# POWER.net
KiCad netlist of a schematic drawn in Altium Designer
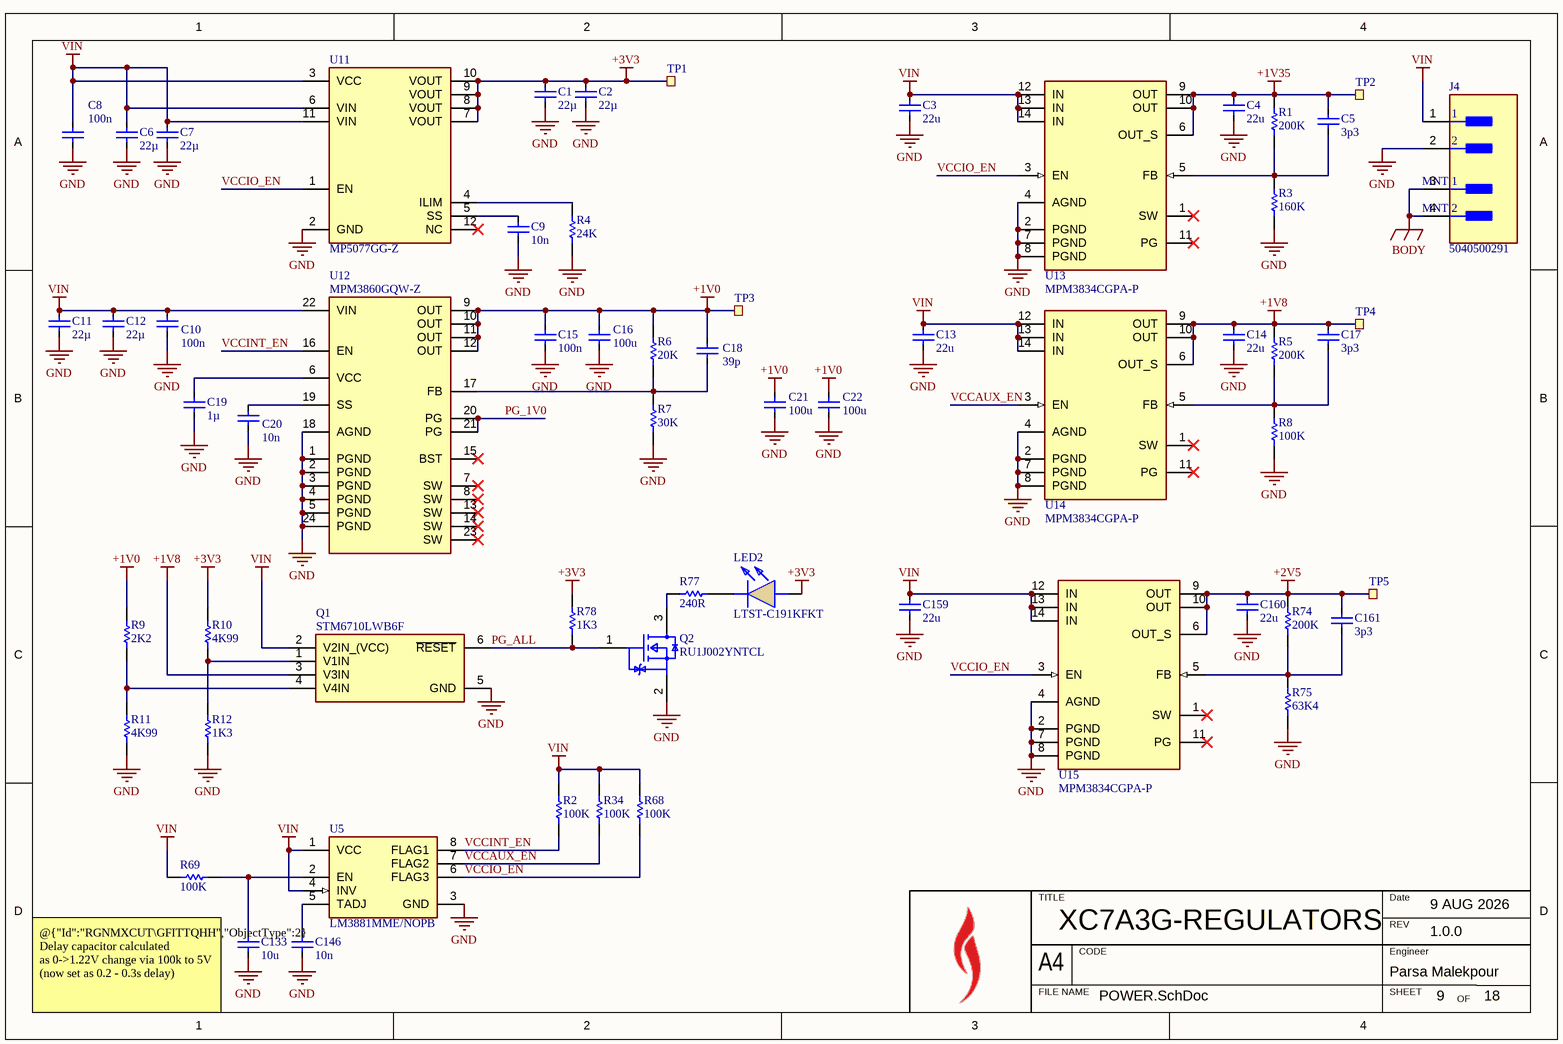
[diagram p0: POWER.SchDoc]

(export (version "E")
  (design (tool "Eeschema 10.0.6"))
  (components
    (comp (ref "C1")
      (value "22µ")
      (footprint "CAPC1608X100X20LL10")
      (description "MLCC 22 uF, ±20%, 6.3 V, -55 to 85 degC, 1608 (0603 Metric), RoHS, Tape and Reel")
      (fields
        (field (name "TOLERANCE") "±20%")
        (field (name "PCN PART NUMBER") "MLCCPartNumberChange30/Nov/2012")
      )
      (libsource (lib "Schlib1") (part "C1608X5R0J226M080AC"))
    )
    (comp (ref "C2")
      (value "22µ")
      (footprint "CAPC1608X100X20LL10")
      (description "MLCC 22 uF, ±20%, 6.3 V, -55 to 85 degC, 1608 (0603 Metric), RoHS, Tape and Reel")
      (fields
        (field (name "TOLERANCE") "±20%")
        (field (name "PCN PART NUMBER") "MLCCPartNumberChange30/Nov/2012")
      )
      (libsource (lib "Schlib1") (part "C1608X5R0J226M080AC"))
    )
    (comp (ref "C3")
      (value "22u")
      (footprint "CAPC1608X100X20LL10")
      (description "MLCC 22 uF, ±20%, 6.3 V, -55 to 85 degC, 1608 (0603 Metric), RoHS, Tape and Reel")
      (fields
        (field (name "TOLERANCE") "±20%")
        (field (name "PCN PART NUMBER") "MLCCPartNumberChange30/Nov/2012")
      )
      (libsource (lib "Schlib1") (part "C1608X5R0J226M080AC"))
    )
    (comp (ref "C4")
      (value "22u")
      (footprint "CAPC1608X100X20LL10")
      (description "MLCC 22 uF, ±20%, 6.3 V, -55 to 85 degC, 1608 (0603 Metric), RoHS, Tape and Reel")
      (fields
        (field (name "TOLERANCE") "±20%")
        (field (name "PCN PART NUMBER") "MLCCPartNumberChange30/Nov/2012")
      )
      (libsource (lib "Schlib1") (part "C1608X5R0J226M080AC"))
    )
    (comp (ref "C5")
      (value "3p3")
      (footprint "PCBLIB1:CAPC1005X55N")
      (description "Capacitor")
      (fields (field (name "PART NUMBER") "CGA2B2C0G1H3R3C050BA"))
      (libsource (lib "Schlib1") (part "CGA2B2C0G1H3R3C050BA"))
    )
    (comp (ref "C6")
      (value "22µ")
      (footprint "CAPC1608X100X20LL10")
      (description "MLCC 22 uF, ±20%, 6.3 V, -55 to 85 degC, 1608 (0603 Metric), RoHS, Tape and Reel")
      (fields
        (field (name "TOLERANCE") "±20%")
        (field (name "PCN PART NUMBER") "MLCCPartNumberChange30/Nov/2012")
      )
      (libsource (lib "Schlib1") (part "C1608X5R0J226M080AC"))
    )
    (comp (ref "C7")
      (value "22µ")
      (footprint "CAPC1608X100X20LL10")
      (description "MLCC 22 uF, ±20%, 6.3 V, -55 to 85 degC, 1608 (0603 Metric), RoHS, Tape and Reel")
      (fields
        (field (name "TOLERANCE") "±20%")
        (field (name "PCN PART NUMBER") "MLCCPartNumberChange30/Nov/2012")
      )
      (libsource (lib "Schlib1") (part "C1608X5R0J226M080AC"))
    )
    (comp (ref "C8")
      (value "100n")
      (footprint "FP-C1005-050-0_05-IPC_C")
      (description "MLCC 100nF ±10% 50V X7R SMD 0402")
      (fields (field (name "VOLTAGE") "50V") (field (name "TOLERANCE") "10%"))
      (libsource (lib "Schlib1") (part "C1005X7R1H104K050BB"))
    )
    (comp (ref "C9")
      (value "10n")
      (footprint "FP-C1005-050-0_05-IPC_C")
      (description "MLCC 10nF ±10% 100V X7S SMD 0402")
      (fields (field (name "TOLERANCE") "10%") (field (name "VOLTAGE") "100V"))
      (libsource (lib "Schlib1") (part "C1005X7S2A103K050BB"))
    )
    (comp (ref "C10")
      (value "100n")
      (footprint "FP-C1005-050-0_05-IPC_C")
      (description "MLCC 100nF ±10% 50V X7R SMD 0402")
      (fields (field (name "VOLTAGE") "50V") (field (name "TOLERANCE") "10%"))
      (libsource (lib "Schlib1") (part "C1005X7R1H104K050BB"))
    )
    (comp (ref "C11")
      (value "22µ")
      (footprint "CAPC1608X100X20LL10")
      (description "MLCC 22 uF, ±20%, 6.3 V, -55 to 85 degC, 1608 (0603 Metric), RoHS, Tape and Reel")
      (fields
        (field (name "TOLERANCE") "±20%")
        (field (name "PCN PART NUMBER") "MLCCPartNumberChange30/Nov/2012")
      )
      (libsource (lib "Schlib1") (part "C1608X5R0J226M080AC"))
    )
    (comp (ref "C12")
      (value "22µ")
      (footprint "CAPC1608X100X20LL10")
      (description "MLCC 22 uF, ±20%, 6.3 V, -55 to 85 degC, 1608 (0603 Metric), RoHS, Tape and Reel")
      (fields
        (field (name "TOLERANCE") "±20%")
        (field (name "PCN PART NUMBER") "MLCCPartNumberChange30/Nov/2012")
      )
      (libsource (lib "Schlib1") (part "C1608X5R0J226M080AC"))
    )
    (comp (ref "C13")
      (value "22u")
      (footprint "CAPC1608X100X20LL10")
      (description "MLCC 22 uF, ±20%, 6.3 V, -55 to 85 degC, 1608 (0603 Metric), RoHS, Tape and Reel")
      (fields
        (field (name "TOLERANCE") "±20%")
        (field (name "PCN PART NUMBER") "MLCCPartNumberChange30/Nov/2012")
      )
      (libsource (lib "Schlib1") (part "C1608X5R0J226M080AC"))
    )
    (comp (ref "C14")
      (value "22u")
      (footprint "CAPC1608X100X20LL10")
      (description "MLCC 22 uF, ±20%, 6.3 V, -55 to 85 degC, 1608 (0603 Metric), RoHS, Tape and Reel")
      (fields
        (field (name "TOLERANCE") "±20%")
        (field (name "PCN PART NUMBER") "MLCCPartNumberChange30/Nov/2012")
      )
      (libsource (lib "Schlib1") (part "C1608X5R0J226M080AC"))
    )
    (comp (ref "C15")
      (value "100n")
      (footprint "FP-C1005-050-0_05-IPC_C")
      (description "MLCC 100nF ±10% 50V X7R SMD 0402")
      (fields (field (name "VOLTAGE") "50V") (field (name "TOLERANCE") "10%"))
      (libsource (lib "Schlib1") (part "C1005X7R1H104K050BB"))
    )
    (comp (ref "C16")
      (value "100u")
      (footprint "FP-C3216-160-0_3-IPC_B")
      (description "MLCC 100uF ±20% 4V X5R SMD 1206")
      (fields (field (name "TOLERANCE") "20%") (field (name "PART NUMBER") "C3216X5R0G107M160AB"))
      (libsource (lib "Schlib1") (part "C3216X5R0G107M160AB"))
    )
    (comp (ref "C17")
      (value "3p3")
      (footprint "PCBLIB1:CAPC1005X55N")
      (description "Capacitor")
      (fields (field (name "PART NUMBER") "CGA2B2C0G1H3R3C050BA"))
      (libsource (lib "Schlib1") (part "CGA2B2C0G1H3R3C050BA"))
    )
    (comp (ref "C18")
      (value "39p")
      (footprint "FP-C1005-050-0_05-IPC_C")
      (description "MLCC 39pF ±5% 50V C0G SMD 0402")
      (fields (field (name "TOLERANCE") "5%") (field (name "PART NUMBER") "C1005C0G1H390J050BA"))
      (libsource (lib "Schlib1") (part "C1005C0G1H390J050BA"))
    )
    (comp (ref "C19")
      (value "1µ")
      (footprint "pcblib1:CAPC1005X55X10NL05")
      (description "MLCC 1 uF, +/- 10%, 10 V, -55 to 85 degC, 0402 (1005 Metric), RoHS, Tape and Reel")
      (fields (field (name "MANUFACTURER") "TDK") (field (name "TOLERANCE") "±10%"))
      (libsource (lib "Schlib1") (part "C1005X5R1A105K050BB"))
    )
    (comp (ref "C20")
      (value "10n")
      (footprint "FP-C1005-050-0_05-IPC_C")
      (description "MLCC 10nF ±10% 100V X7S SMD 0402")
      (fields (field (name "TOLERANCE") "10%") (field (name "VOLTAGE") "100V"))
      (libsource (lib "Schlib1") (part "C1005X7S2A103K050BB"))
    )
    (comp (ref "C21")
      (value "100u")
      (footprint "FP-C3216-160-0_3-IPC_B")
      (description "MLCC 100uF ±20% 4V X5R SMD 1206")
      (fields (field (name "TOLERANCE") "20%") (field (name "PART NUMBER") "C3216X5R0G107M160AB"))
      (libsource (lib "Schlib1") (part "C3216X5R0G107M160AB"))
    )
    (comp (ref "C22")
      (value "100u")
      (footprint "FP-C3216-160-0_3-IPC_B")
      (description "MLCC 100uF ±20% 4V X5R SMD 1206")
      (fields (field (name "TOLERANCE") "20%") (field (name "PART NUMBER") "C3216X5R0G107M160AB"))
      (libsource (lib "Schlib1") (part "C3216X5R0G107M160AB"))
    )
    (comp (ref "C133")
      (value "10u")
      (footprint "FP-C1608-080-0_1-IPC_C")
      (description "MLCC 10μF ±10% 6.3V JB SMD 0603")
      (fields (field (name "TOLERANCE") "10%") (field (name "Comment") "C1608JB0J106K080AB"))
      (libsource (lib "Schlib1") (part "C1608JB0J106K080AB"))
    )
    (comp (ref "C146")
      (value "10n")
      (footprint "FP-C1005-050-0_05-IPC_C")
      (description "MLCC 10nF ±10% 100V X7S SMD 0402")
      (fields (field (name "TOLERANCE") "10%") (field (name "VOLTAGE") "100V"))
      (libsource (lib "Schlib1") (part "C1005X7S2A103K050BB"))
    )
    (comp (ref "C159")
      (value "22u")
      (footprint "CAPC1608X100X20NL10")
      (description "MLCC 22 uF, ±20%, 6.3 V, -55 to 85 degC, 1608 (0603 Metric), RoHS, Tape and Reel")
      (fields
        (field (name "TOLERANCE") "±20%")
        (field (name "PCN PART NUMBER") "MLCCPartNumberChange30/Nov/2012")
      )
      (libsource (lib "Schlib1") (part "C1608X5R0J226M080AC"))
    )
    (comp (ref "C160")
      (value "22u")
      (footprint "CAPC1608X100X20LL10")
      (description "MLCC 22 uF, ±20%, 6.3 V, -55 to 85 degC, 1608 (0603 Metric), RoHS, Tape and Reel")
      (fields
        (field (name "TOLERANCE") "±20%")
        (field (name "PCN PART NUMBER") "MLCCPartNumberChange30/Nov/2012")
      )
      (libsource (lib "Schlib1") (part "C1608X5R0J226M080AC"))
    )
    (comp (ref "C161")
      (value "3p3")
      (footprint "PCBLIB1:CAPC1005X55N")
      (description "Capacitor")
      (fields (field (name "PART NUMBER") "CGA2B2C0G1H3R3C050BA"))
      (libsource (lib "Schlib1") (part "CGA2B2C0G1H3R3C050BA"))
    )
    (comp (ref "J4")
      (value "5040500291")
      (footprint "FP-5040500291-MFG")
      (description "CONN HEADER SMD R/A 2POS 1.5MM")
      (fields
        (field (name "OCTOPART") "https://octopart.com/504050-0291-molex-99548498")
        (field (name "MANUFACTURER") "Molex")
      )
      (libsource (lib "Schlib1") (part "5040500291"))
    )
    (comp (ref "LED2")
      (value "LTST-C191KFKT")
      (footprint "LEDC1608X55N")
      (description "LED")
      (fields (field (name "MOUSER PART NUMBER") "859-LTST-C191KFKT") (field (name "MANUFACTURER") "Lite-On"))
      (libsource (lib "Schlib1") (part "LTST-C191KFKT"))
    )
    (comp (ref "Q1")
      (value "STM6710LWB6F")
      (footprint "SOT95P280X145-6N")
      (description "Transistor")
      (fields (field (name "MOUSER PART NUMBER") "511-STM6710LWB6F"))
      (libsource (lib "Schlib1") (part "STM6710LWB6F"))
    )
    (comp (ref "Q2")
      (value "RU1J002YNTCL")
      (footprint "FP-UMT3F-MFG")
      (description "MOSFET N-CH 50V 0.2A UMT3F")
      (fields
        (field (name "MANUFACTURER") "Rohm")
        (field (name "OCTOPART") "https://octopart.com/ru1j002yntcl-rohm-47197697")
      )
      (libsource (lib "Schlib1") (part "RU1J002YNTCL"))
    )
    (comp (ref "R1")
      (value "200K")
      (footprint "RESC1005X40X25NL05T10")
      (fields (field (name "PART NUMBER") "RC0402FR-07200KL") (field (name "MANUFACTURER") "Yageo / Phycomp"))
      (libsource (lib "Schlib1") (part "RC0402FR-07200KL"))
    )
    (comp (ref "R2")
      (value "100K")
      (footprint "RESC1005X40X25LL05T10")
      (fields (field (name "PART NUMBER") "RC0402FR-07100KL") (field (name "MANUFACTURER") "Yageo / Phycomp"))
      (libsource (lib "Schlib1") (part "RC0402FR-07100KL"))
    )
    (comp (ref "R3")
      (value "160K")
      (footprint "RESC1005X40X25NL05T10")
      (fields (field (name "PART NUMBER") "RC0402FR-07160KL") (field (name "MANUFACTURER") "Yageo / Phycomp"))
      (libsource (lib "Schlib1") (part "RC0402FR-07160KL"))
    )
    (comp (ref "R4")
      (value "24K")
      (footprint "RESC1005X40X25LL05T10")
      (fields (field (name "MANUFACTURER") "Yageo / Phycomp") (field (name "PART NUMBER") "RC0402FR-0724KL"))
      (libsource (lib "Schlib1") (part "RC0402FR-0724KL"))
    )
    (comp (ref "R5")
      (value "200K")
      (footprint "RESC1005X40X25LL05T10")
      (fields (field (name "PART NUMBER") "RC0402FR-07200KL") (field (name "MANUFACTURER") "Yageo / Phycomp"))
      (libsource (lib "Schlib1") (part "RC0402FR-07200KL"))
    )
    (comp (ref "R6")
      (value "20K")
      (footprint "RESC1005X40X25LL05T10")
      (fields (field (name "MANUFACTURER") "Yageo / Phycomp") (field (name "PART NUMBER") "RC0402FR-0720KL"))
      (libsource (lib "Schlib1") (part "RC0402FR-0720KL"))
    )
    (comp (ref "R7")
      (value "30K")
      (footprint "RESC1005X40X25LL05T10")
      (fields (field (name "MANUFACTURER") "Yageo / Phycomp") (field (name "PART NUMBER") "RC0402FR-0730KL"))
      (libsource (lib "Schlib1") (part "RC0402FR-0730KL"))
    )
    (comp (ref "R8")
      (value "100K")
      (footprint "RESC1005X40X25LL05T10")
      (fields (field (name "PART NUMBER") "RC0402FR-07100KL") (field (name "MANUFACTURER") "Yageo / Phycomp"))
      (libsource (lib "Schlib1") (part "RC0402FR-07100KL"))
    )
    (comp (ref "R9")
      (value "2K2")
      (footprint "RESC1005X40X25LL05T10")
      (fields (field (name "MANUFACTURER") "Yageo / Phycomp") (field (name "PART NUMBER") "RC0402FR-072K2L"))
      (libsource (lib "Schlib1") (part "RC0402FR-072K2L"))
    )
    (comp (ref "R10")
      (value "4K99")
      (footprint "RESC1005X40X25LL05T10")
      (fields (field (name "MANUFACTURER") "Yageo / Phycomp") (field (name "PART NUMBER") "RC0402FR-074K99L"))
      (libsource (lib "Schlib1") (part "RC0402FR-074K99L"))
    )
    (comp (ref "R11")
      (value "4K99")
      (footprint "PCBLIB1:RESC1005X40X25LL05T10")
      (fields (field (name "MANUFACTURER") "Yageo / Phycomp") (field (name "PART NUMBER") "RC0402FR-074K99L"))
      (libsource (lib "Schlib1") (part "RC0402FR-074K99L"))
    )
    (comp (ref "R12")
      (value "1K3")
      (footprint "RESC1005X40X25LL05T10")
      (fields (field (name "MANUFACTURER") "Yageo / Phycomp") (field (name "PART NUMBER") "RC0402FR-071K3L"))
      (libsource (lib "Schlib1") (part "RC0402FR-071K3L"))
    )
    (comp (ref "R34")
      (value "100K")
      (footprint "RESC1005X40X25LL05T10")
      (fields (field (name "PART NUMBER") "RC0402FR-07100KL") (field (name "MANUFACTURER") "Yageo / Phycomp"))
      (libsource (lib "Schlib1") (part "RC0402FR-07100KL"))
    )
    (comp (ref "R68")
      (value "100K")
      (footprint "RESC1005X40X25LL05T10")
      (fields (field (name "PART NUMBER") "RC0402FR-07100KL") (field (name "MANUFACTURER") "Yageo / Phycomp"))
      (libsource (lib "Schlib1") (part "RC0402FR-07100KL"))
    )
    (comp (ref "R69")
      (value "100K")
      (footprint "RESC1005X40X25NL05T10")
      (fields (field (name "PART NUMBER") "RC0402FR-07100KL") (field (name "MANUFACTURER") "Yageo / Phycomp"))
      (libsource (lib "Schlib1") (part "RC0402FR-07100KL"))
    )
    (comp (ref "R74")
      (value "200K")
      (footprint "RESC1005X40X25NL05T10")
      (fields (field (name "PART NUMBER") "RC0402FR-07200KL") (field (name "MANUFACTURER") "Yageo / Phycomp"))
      (libsource (lib "Schlib1") (part "RC0402FR-07200KL"))
    )
    (comp (ref "R75")
      (value "63K4")
      (footprint "RESC1005X40X25ML05T10")
      (fields (field (name "MANUFACTURER") "Yageo / Phycomp") (field (name "PART NUMBER") "RC0402FR-0763K4L"))
      (libsource (lib "Schlib1") (part "RC0402FR-0763K4L"))
    )
    (comp (ref "R77")
      (value "240R")
      (footprint "pcblib1:RESC1005X40X25LL05T10")
      (description "240R 0.063W 1% 0402 (1005 Metric)  SMD")
      (fields (field (name "POWER") "0.063 W") (field (name "TOLERANCE") "1 %"))
      (libsource (lib "Schlib1") (part "RC0402FR-07240RL"))
    )
    (comp (ref "R78")
      (value "1K3")
      (footprint "RESC1005X40X25LL05T10")
      (fields (field (name "MANUFACTURER") "Yageo / Phycomp") (field (name "PART NUMBER") "RC0402FR-071K3L"))
      (libsource (lib "Schlib1") (part "RC0402FR-071K3L"))
    )
    (comp (ref "TP1")
      (value "Ø1.0mm,SMD")
      (footprint "TP_SMD_Ø1.0mm")
      (description "1.0mm circular SMD testpad")
      (fields
        (field (name "PART NUMBER") "TP_SMD_Ø1.0MM")
        (field (name "MANUFACTURER") "Nordic Semiconductor")
      )
      (libsource (lib "ParsaLibrary") (part "TP_SMD_Ø1.0MM"))
    )
    (comp (ref "TP2")
      (value "Ø1.0mm,SMD")
      (footprint "TP_SMD_Ø1.0mm")
      (description "1.0mm circular SMD testpad")
      (fields
        (field (name "PART NUMBER") "TP_SMD_Ø1.0MM")
        (field (name "MANUFACTURER") "Nordic Semiconductor")
      )
      (libsource (lib "ParsaLibrary") (part "TP_SMD_Ø1.0MM"))
    )
    (comp (ref "TP3")
      (value "Ø1.0mm,SMD")
      (footprint "TP_SMD_Ø1.0mm")
      (description "1.0mm circular SMD testpad")
      (fields
        (field (name "PART NUMBER") "TP_SMD_Ø1.0MM")
        (field (name "MANUFACTURER") "Nordic Semiconductor")
      )
      (libsource (lib "ParsaLibrary") (part "TP_SMD_Ø1.0MM"))
    )
    (comp (ref "TP4")
      (value "Ø1.0mm,SMD")
      (footprint "TP_SMD_Ø1.0mm")
      (description "1.0mm circular SMD testpad")
      (fields
        (field (name "PART NUMBER") "TP_SMD_Ø1.0MM")
        (field (name "MANUFACTURER") "Nordic Semiconductor")
      )
      (libsource (lib "ParsaLibrary") (part "TP_SMD_Ø1.0MM"))
    )
    (comp (ref "TP5")
      (value "Ø1.0mm,SMD")
      (footprint "TP_SMD_Ø1.0mm")
      (description "1.0mm circular SMD testpad")
      (fields
        (field (name "PART NUMBER") "TP_SMD_Ø1.0MM")
        (field (name "MANUFACTURER") "Nordic Semiconductor")
      )
      (libsource (lib "ParsaLibrary") (part "TP_SMD_Ø1.0MM"))
    )
    (comp (ref "U5")
      (value "LM3881MME/NOPB")
      (footprint "FP-DGK0008A-MFG")
      (description "IC POWER SUPPLY SEQUENCER 8VSSOP")
      (fields
        (field (name "OCTOPART") "https://octopart.com/lm3881mme%2Fnopb-texas+instruments-24814197")
        (field (name "MANUFACTURER") "Texas Instruments")
      )
      (libsource (lib "Schlib1") (part "LM3881MME/NOPB"))
    )
    (comp (ref "U11")
      (value "MP5077GG-Z")
      (footprint "MP5077GGZ")
      (description "Integrated Circuit")
      (fields (field (name "MOUSER PART NUMBER") "946-MP5077GG-Z"))
      (libsource (lib "Schlib1") (part "MP5077GG-Z"))
    )
    (comp (ref "U12")
      (value "MPM3860GQW-Z")
      (footprint "MPM3650CGQWZ")
      (description "Integrated Circuit")
      (fields (field (name "MOUSER PART NUMBER") "946-MPM3860GQW-Z"))
      (libsource (lib "Schlib1") (part "MPM3860GQW-Z"))
    )
    (comp (ref "U13")
      (value "MPM3834CGPA-P")
      (footprint "MPM3834CGPAP")
      (description "Integrated Circuit")
      (fields (field (name "MOUSER PART NUMBER") "946-MPM3834CGPA-P"))
      (libsource (lib "Schlib1") (part "MPM3834CGPA-P"))
    )
    (comp (ref "U14")
      (value "MPM3834CGPA-P")
      (footprint "MPM3834CGPAP")
      (description "Integrated Circuit")
      (fields (field (name "MOUSER PART NUMBER") "946-MPM3834CGPA-P"))
      (libsource (lib "Schlib1") (part "MPM3834CGPA-P"))
    )
    (comp (ref "U15")
      (value "MPM3834CGPA-P")
      (footprint "MPM3834CGPAP")
      (description "Integrated Circuit")
      (fields (field (name "MOUSER PART NUMBER") "946-MPM3834CGPA-P"))
      (libsource (lib "Schlib1") (part "MPM3834CGPA-P"))
    )
  )
  (nets
    (net (code "1") (name "+1V0") (class "Default")
      (node (ref "C15") (pin "1") (pinfunction "1_1") (pintype "passive"))
      (node (ref "C16") (pin "2") (pinfunction "2_2") (pintype "passive"))
      (node (ref "C18") (pin "2") (pinfunction "2_2") (pintype "passive"))
      (node (ref "C21") (pin "2") (pinfunction "2_2") (pintype "passive"))
      (node (ref "C22") (pin "2") (pinfunction "2_2") (pintype "passive"))
      (node (ref "R6") (pin "1") (pinfunction "1_1") (pintype "passive"))
      (node (ref "R9") (pin "1") (pinfunction "1_1") (pintype "passive"))
      (node (ref "TP3") (pin "1") (pinfunction "1_1") (pintype "passive"))
      (node (ref "U12") (pin "10") (pinfunction "OUT_10") (pintype "passive"))
      (node (ref "U12") (pin "11") (pinfunction "OUT_11") (pintype "passive"))
      (node (ref "U12") (pin "12") (pinfunction "OUT_12") (pintype "passive"))
      (node (ref "U12") (pin "9") (pinfunction "OUT_9") (pintype "passive"))
    )
    (net (code "2") (name "+1V8") (class "Default")
      (node (ref "C14") (pin "1") (pinfunction "1_1") (pintype "passive"))
      (node (ref "C17") (pin "1") (pinfunction "1_1") (pintype "passive"))
      (node (ref "Q1") (pin "3") (pinfunction "V3IN_3") (pintype "passive"))
      (node (ref "R5") (pin "1") (pinfunction "1_1") (pintype "passive"))
      (node (ref "TP4") (pin "1") (pinfunction "1_1") (pintype "passive"))
      (node (ref "U14") (pin "10") (pinfunction "OUT_10") (pintype "power_in"))
      (node (ref "U14") (pin "6") (pinfunction "OUT_S_6") (pintype "passive"))
      (node (ref "U14") (pin "9") (pinfunction "OUT_9") (pintype "power_in"))
    )
    (net (code "3") (name "+1V35") (class "Default")
      (node (ref "C4") (pin "1") (pinfunction "1_1") (pintype "passive"))
      (node (ref "C5") (pin "1") (pinfunction "1_1") (pintype "passive"))
      (node (ref "R1") (pin "1") (pinfunction "1_1") (pintype "passive"))
      (node (ref "TP2") (pin "1") (pinfunction "1_1") (pintype "passive"))
      (node (ref "U13") (pin "10") (pinfunction "OUT_10") (pintype "power_in"))
      (node (ref "U13") (pin "6") (pinfunction "OUT_S_6") (pintype "passive"))
      (node (ref "U13") (pin "9") (pinfunction "OUT_9") (pintype "power_in"))
    )
    (net (code "4") (name "+2V5") (class "Default")
      (node (ref "C160") (pin "1") (pinfunction "1_1") (pintype "passive"))
      (node (ref "C161") (pin "1") (pinfunction "1_1") (pintype "passive"))
      (node (ref "R74") (pin "1") (pinfunction "1_1") (pintype "passive"))
      (node (ref "TP5") (pin "1") (pinfunction "1_1") (pintype "passive"))
      (node (ref "U15") (pin "10") (pinfunction "OUT_10") (pintype "power_in"))
      (node (ref "U15") (pin "6") (pinfunction "OUT_S_6") (pintype "passive"))
      (node (ref "U15") (pin "9") (pinfunction "OUT_9") (pintype "power_in"))
    )
    (net (code "5") (name "+3V3") (class "Default")
      (node (ref "C1") (pin "1") (pinfunction "1_1") (pintype "passive"))
      (node (ref "C2") (pin "1") (pinfunction "1_1") (pintype "passive"))
      (node (ref "LED2") (pin "2") (pinfunction "A_2") (pintype "passive"))
      (node (ref "R10") (pin "1") (pinfunction "1_1") (pintype "passive"))
      (node (ref "R78") (pin "1") (pinfunction "1_1") (pintype "passive"))
      (node (ref "TP1") (pin "1") (pinfunction "1_1") (pintype "passive"))
      (node (ref "U11") (pin "10") (pinfunction "VOUT_10") (pintype "passive"))
      (node (ref "U11") (pin "7") (pinfunction "VOUT_7") (pintype "passive"))
      (node (ref "U11") (pin "8") (pinfunction "VOUT_8") (pintype "passive"))
      (node (ref "U11") (pin "9") (pinfunction "VOUT_9") (pintype "passive"))
    )
    (net (code "6") (name "/PG_1V0") (class "Default")
      (node (ref "U12") (pin "20") (pinfunction "PG_20") (pintype "passive"))
      (node (ref "U12") (pin "21") (pinfunction "PG_21") (pintype "passive"))
    )
    (net (code "7") (name "/PG_ALL") (class "Default")
      (node (ref "Q1") (pin "6") (pinfunction "~{RESET}_6") (pintype "passive"))
      (node (ref "Q2") (pin "1") (pinfunction "G_1") (pintype "passive"))
      (node (ref "R78") (pin "2") (pinfunction "2_2") (pintype "passive"))
    )
    (net (code "8") (name "/VCCAUX_EN") (class "Default")
      (node (ref "R34") (pin "2") (pinfunction "2_2") (pintype "passive"))
      (node (ref "U14") (pin "3") (pinfunction "EN_3") (pintype "input"))
      (node (ref "U5") (pin "7") (pinfunction "FLAG2_7") (pintype "open_collector"))
    )
    (net (code "9") (name "/VCCINT_EN") (class "Default")
      (node (ref "R2") (pin "2") (pinfunction "2_2") (pintype "passive"))
      (node (ref "U12") (pin "16") (pinfunction "EN_16") (pintype "passive"))
      (node (ref "U5") (pin "8") (pinfunction "FLAG1_8") (pintype "open_collector"))
    )
    (net (code "10") (name "/VCCIO_EN") (class "Default")
      (node (ref "R68") (pin "2") (pinfunction "2_2") (pintype "passive"))
      (node (ref "U11") (pin "1") (pinfunction "EN_1") (pintype "passive"))
      (node (ref "U13") (pin "3") (pinfunction "EN_3") (pintype "input"))
      (node (ref "U15") (pin "3") (pinfunction "EN_3") (pintype "input"))
      (node (ref "U5") (pin "6") (pinfunction "FLAG3_6") (pintype "open_collector"))
    )
    (net (code "11") (name "BODY") (class "Default")
      (node (ref "J4") (pin "3") (pinfunction "MNT_1_3") (pintype "passive"))
      (node (ref "J4") (pin "4") (pinfunction "MNT_2_4") (pintype "passive"))
    )
    (net (code "12") (name "GND") (class "Default")
      (node (ref "C1") (pin "2") (pinfunction "2_2") (pintype "passive"))
      (node (ref "C10") (pin "1") (pinfunction "1_1") (pintype "passive"))
      (node (ref "C11") (pin "2") (pinfunction "2_2") (pintype "passive"))
      (node (ref "C12") (pin "2") (pinfunction "2_2") (pintype "passive"))
      (node (ref "C13") (pin "2") (pinfunction "2_2") (pintype "passive"))
      (node (ref "C133") (pin "2") (pinfunction "2_2") (pintype "passive"))
      (node (ref "C14") (pin "2") (pinfunction "2_2") (pintype "passive"))
      (node (ref "C146") (pin "2") (pinfunction "2_2") (pintype "passive"))
      (node (ref "C15") (pin "2") (pinfunction "2_2") (pintype "passive"))
      (node (ref "C159") (pin "2") (pinfunction "2_2") (pintype "passive"))
      (node (ref "C16") (pin "1") (pinfunction "1_1") (pintype "passive"))
      (node (ref "C160") (pin "2") (pinfunction "2_2") (pintype "passive"))
      (node (ref "C19") (pin "2") (pinfunction "2_2") (pintype "passive"))
      (node (ref "C2") (pin "2") (pinfunction "2_2") (pintype "passive"))
      (node (ref "C20") (pin "1") (pinfunction "1_1") (pintype "passive"))
      (node (ref "C21") (pin "1") (pinfunction "1_1") (pintype "passive"))
      (node (ref "C22") (pin "1") (pinfunction "1_1") (pintype "passive"))
      (node (ref "C3") (pin "2") (pinfunction "2_2") (pintype "passive"))
      (node (ref "C4") (pin "2") (pinfunction "2_2") (pintype "passive"))
      (node (ref "C6") (pin "2") (pinfunction "2_2") (pintype "passive"))
      (node (ref "C7") (pin "2") (pinfunction "2_2") (pintype "passive"))
      (node (ref "C8") (pin "1") (pinfunction "1_1") (pintype "passive"))
      (node (ref "C9") (pin "2") (pinfunction "2_2") (pintype "passive"))
      (node (ref "J4") (pin "2") (pinfunction "2_2") (pintype "passive"))
      (node (ref "Q1") (pin "5") (pinfunction "GND_5") (pintype "passive"))
      (node (ref "Q2") (pin "2") (pinfunction "S_2") (pintype "passive"))
      (node (ref "R11") (pin "2") (pinfunction "2_2") (pintype "passive"))
      (node (ref "R12") (pin "1") (pinfunction "1_1") (pintype "passive"))
      (node (ref "R3") (pin "2") (pinfunction "2_2") (pintype "passive"))
      (node (ref "R4") (pin "2") (pinfunction "2_2") (pintype "passive"))
      (node (ref "R7") (pin "2") (pinfunction "2_2") (pintype "passive"))
      (node (ref "R75") (pin "2") (pinfunction "2_2") (pintype "passive"))
      (node (ref "R8") (pin "2") (pinfunction "2_2") (pintype "passive"))
      (node (ref "U11") (pin "2") (pinfunction "GND_2") (pintype "passive"))
      (node (ref "U12") (pin "1") (pinfunction "PGND_1") (pintype "passive"))
      (node (ref "U12") (pin "18") (pinfunction "AGND_18") (pintype "passive"))
      (node (ref "U12") (pin "2") (pinfunction "PGND_2") (pintype "passive"))
      (node (ref "U12") (pin "24") (pinfunction "PGND_24") (pintype "passive"))
      (node (ref "U12") (pin "3") (pinfunction "PGND_3") (pintype "passive"))
      (node (ref "U12") (pin "4") (pinfunction "PGND_4") (pintype "passive"))
      (node (ref "U12") (pin "5") (pinfunction "PGND_5") (pintype "passive"))
      (node (ref "U13") (pin "2") (pinfunction "PGND_2") (pintype "power_in"))
      (node (ref "U13") (pin "4") (pinfunction "AGND_4") (pintype "passive"))
      (node (ref "U13") (pin "7") (pinfunction "PGND_7") (pintype "power_in"))
      (node (ref "U13") (pin "8") (pinfunction "PGND_8") (pintype "power_in"))
      (node (ref "U14") (pin "2") (pinfunction "PGND_2") (pintype "power_in"))
      (node (ref "U14") (pin "4") (pinfunction "AGND_4") (pintype "passive"))
      (node (ref "U14") (pin "7") (pinfunction "PGND_7") (pintype "power_in"))
      (node (ref "U14") (pin "8") (pinfunction "PGND_8") (pintype "power_in"))
      (node (ref "U15") (pin "2") (pinfunction "PGND_2") (pintype "power_in"))
      (node (ref "U15") (pin "4") (pinfunction "AGND_4") (pintype "passive"))
      (node (ref "U15") (pin "7") (pinfunction "PGND_7") (pintype "power_in"))
      (node (ref "U15") (pin "8") (pinfunction "PGND_8") (pintype "power_in"))
      (node (ref "U5") (pin "3") (pinfunction "GND_3") (pintype "power_in"))
    )
    (net (code "13") (name "Net-(LED2-K)") (class "Default")
      (node (ref "LED2") (pin "1") (pinfunction "K_1") (pintype "passive"))
      (node (ref "R77") (pin "1") (pinfunction "1_1") (pintype "passive"))
    )
    (net (code "14") (name "Net-(Q1-V1IN)") (class "Default")
      (node (ref "Q1") (pin "1") (pinfunction "V1IN_1") (pintype "passive"))
      (node (ref "R10") (pin "2") (pinfunction "2_2") (pintype "passive"))
      (node (ref "R12") (pin "2") (pinfunction "2_2") (pintype "passive"))
    )
    (net (code "15") (name "Net-(Q1-V4IN)") (class "Default")
      (node (ref "Q1") (pin "4") (pinfunction "V4IN_4") (pintype "passive"))
      (node (ref "R11") (pin "1") (pinfunction "1_1") (pintype "passive"))
      (node (ref "R9") (pin "2") (pinfunction "2_2") (pintype "passive"))
    )
    (net (code "16") (name "Net-(Q2-D)") (class "Default")
      (node (ref "Q2") (pin "3") (pinfunction "D_3") (pintype "passive"))
      (node (ref "R77") (pin "2") (pinfunction "2_2") (pintype "passive"))
    )
    (net (code "17") (name "Net-(U5-EN)") (class "Default")
      (node (ref "C133") (pin "1") (pinfunction "1_1") (pintype "passive"))
      (node (ref "R69") (pin "2") (pinfunction "2_2") (pintype "passive"))
      (node (ref "U5") (pin "2") (pinfunction "EN_2") (pintype "passive"))
    )
    (net (code "18") (name "Net-(U5-TADJ)") (class "Default")
      (node (ref "C146") (pin "1") (pinfunction "1_1") (pintype "passive"))
      (node (ref "U5") (pin "5") (pinfunction "TADJ_5") (pintype "passive"))
    )
    (net (code "19") (name "Net-(U11-ILIM)") (class "Default")
      (node (ref "R4") (pin "1") (pinfunction "1_1") (pintype "passive"))
      (node (ref "U11") (pin "4") (pinfunction "ILIM_4") (pintype "passive"))
    )
    (net (code "20") (name "Net-(U11-SS)") (class "Default")
      (node (ref "C9") (pin "1") (pinfunction "1_1") (pintype "passive"))
      (node (ref "U11") (pin "5") (pinfunction "SS_5") (pintype "passive"))
    )
    (net (code "21") (name "Net-(U12-FB)") (class "Default")
      (node (ref "C18") (pin "1") (pinfunction "1_1") (pintype "passive"))
      (node (ref "R6") (pin "2") (pinfunction "2_2") (pintype "passive"))
      (node (ref "R7") (pin "1") (pinfunction "1_1") (pintype "passive"))
      (node (ref "U12") (pin "17") (pinfunction "FB_17") (pintype "passive"))
    )
    (net (code "22") (name "Net-(U12-SS)") (class "Default")
      (node (ref "C20") (pin "2") (pinfunction "2_2") (pintype "passive"))
      (node (ref "U12") (pin "19") (pinfunction "SS_19") (pintype "passive"))
    )
    (net (code "23") (name "Net-(U12-VCC)") (class "Default")
      (node (ref "C19") (pin "1") (pinfunction "1_1") (pintype "passive"))
      (node (ref "U12") (pin "6") (pinfunction "VCC_6") (pintype "passive"))
    )
    (net (code "24") (name "Net-(U13-FB)") (class "Default")
      (node (ref "C5") (pin "2") (pinfunction "2_2") (pintype "passive"))
      (node (ref "R1") (pin "2") (pinfunction "2_2") (pintype "passive"))
      (node (ref "R3") (pin "1") (pinfunction "1_1") (pintype "passive"))
      (node (ref "U13") (pin "5") (pinfunction "FB_5") (pintype "input"))
    )
    (net (code "25") (name "Net-(U14-FB)") (class "Default")
      (node (ref "C17") (pin "2") (pinfunction "2_2") (pintype "passive"))
      (node (ref "R5") (pin "2") (pinfunction "2_2") (pintype "passive"))
      (node (ref "R8") (pin "1") (pinfunction "1_1") (pintype "passive"))
      (node (ref "U14") (pin "5") (pinfunction "FB_5") (pintype "input"))
    )
    (net (code "26") (name "Net-(U15-FB)") (class "Default")
      (node (ref "C161") (pin "2") (pinfunction "2_2") (pintype "passive"))
      (node (ref "R74") (pin "2") (pinfunction "2_2") (pintype "passive"))
      (node (ref "R75") (pin "1") (pinfunction "1_1") (pintype "passive"))
      (node (ref "U15") (pin "5") (pinfunction "FB_5") (pintype "input"))
    )
    (net (code "27") (name "VIN") (class "Default")
      (node (ref "C10") (pin "2") (pinfunction "2_2") (pintype "passive"))
      (node (ref "C11") (pin "1") (pinfunction "1_1") (pintype "passive"))
      (node (ref "C12") (pin "1") (pinfunction "1_1") (pintype "passive"))
      (node (ref "C13") (pin "1") (pinfunction "1_1") (pintype "passive"))
      (node (ref "C159") (pin "1") (pinfunction "1_1") (pintype "passive"))
      (node (ref "C3") (pin "1") (pinfunction "1_1") (pintype "passive"))
      (node (ref "C6") (pin "1") (pinfunction "1_1") (pintype "passive"))
      (node (ref "C7") (pin "1") (pinfunction "1_1") (pintype "passive"))
      (node (ref "C8") (pin "2") (pinfunction "2_2") (pintype "passive"))
      (node (ref "J4") (pin "1") (pinfunction "1_1") (pintype "passive"))
      (node (ref "Q1") (pin "2") (pinfunction "V2IN_(VCC)_2") (pintype "passive"))
      (node (ref "R2") (pin "1") (pinfunction "1_1") (pintype "passive"))
      (node (ref "R34") (pin "1") (pinfunction "1_1") (pintype "passive"))
      (node (ref "R68") (pin "1") (pinfunction "1_1") (pintype "passive"))
      (node (ref "R69") (pin "1") (pinfunction "1_1") (pintype "passive"))
      (node (ref "U11") (pin "11") (pinfunction "VIN_11") (pintype "passive"))
      (node (ref "U11") (pin "3") (pinfunction "VCC_3") (pintype "passive"))
      (node (ref "U11") (pin "6") (pinfunction "VIN_6") (pintype "passive"))
      (node (ref "U12") (pin "22") (pinfunction "VIN_22") (pintype "passive"))
      (node (ref "U13") (pin "12") (pinfunction "IN_12") (pintype "power_in"))
      (node (ref "U13") (pin "13") (pinfunction "IN_13") (pintype "power_in"))
      (node (ref "U13") (pin "14") (pinfunction "IN_14") (pintype "power_in"))
      (node (ref "U14") (pin "12") (pinfunction "IN_12") (pintype "power_in"))
      (node (ref "U14") (pin "13") (pinfunction "IN_13") (pintype "power_in"))
      (node (ref "U14") (pin "14") (pinfunction "IN_14") (pintype "power_in"))
      (node (ref "U15") (pin "12") (pinfunction "IN_12") (pintype "power_in"))
      (node (ref "U15") (pin "13") (pinfunction "IN_13") (pintype "power_in"))
      (node (ref "U15") (pin "14") (pinfunction "IN_14") (pintype "power_in"))
      (node (ref "U5") (pin "1") (pinfunction "VCC_1") (pintype "power_in"))
      (node (ref "U5") (pin "4") (pinfunction "INV_4") (pintype "input"))
    )
    (net (code "28") (name "unconnected-(U11-NC-Pad12)") (class "Default")
      (node (ref "U11") (pin "12") (pinfunction "NC_12") (pintype "passive+no_connect"))
    )
    (net (code "29") (name "unconnected-(U12-BST-Pad15)") (class "Default")
      (node (ref "U12") (pin "15") (pinfunction "BST_15") (pintype "passive+no_connect"))
    )
    (net (code "30") (name "unconnected-(U12-SW-Pad7)") (class "Default")
      (node (ref "U12") (pin "7") (pinfunction "SW_7") (pintype "passive+no_connect"))
    )
    (net (code "31") (name "unconnected-(U12-SW-Pad8)") (class "Default")
      (node (ref "U12") (pin "8") (pinfunction "SW_8") (pintype "passive+no_connect"))
    )
    (net (code "32") (name "unconnected-(U12-SW-Pad13)") (class "Default")
      (node (ref "U12") (pin "13") (pinfunction "SW_13") (pintype "passive+no_connect"))
    )
    (net (code "33") (name "unconnected-(U12-SW-Pad14)") (class "Default")
      (node (ref "U12") (pin "14") (pinfunction "SW_14") (pintype "passive+no_connect"))
    )
    (net (code "34") (name "unconnected-(U12-SW-Pad23)") (class "Default")
      (node (ref "U12") (pin "23") (pinfunction "SW_23") (pintype "passive+no_connect"))
    )
    (net (code "35") (name "unconnected-(U13-PG-Pad11)") (class "Default")
      (node (ref "U13") (pin "11") (pinfunction "PG_11") (pintype "passive+no_connect"))
    )
    (net (code "36") (name "unconnected-(U13-SW-Pad1)") (class "Default")
      (node (ref "U13") (pin "1") (pinfunction "SW_1") (pintype "passive+no_connect"))
    )
    (net (code "37") (name "unconnected-(U14-PG-Pad11)") (class "Default")
      (node (ref "U14") (pin "11") (pinfunction "PG_11") (pintype "passive+no_connect"))
    )
    (net (code "38") (name "unconnected-(U14-SW-Pad1)") (class "Default")
      (node (ref "U14") (pin "1") (pinfunction "SW_1") (pintype "passive+no_connect"))
    )
    (net (code "39") (name "unconnected-(U15-PG-Pad11)") (class "Default")
      (node (ref "U15") (pin "11") (pinfunction "PG_11") (pintype "passive+no_connect"))
    )
    (net (code "40") (name "unconnected-(U15-SW-Pad1)") (class "Default")
      (node (ref "U15") (pin "1") (pinfunction "SW_1") (pintype "passive+no_connect"))
    )
  )
)
